# SCH_N64_SpyDVI_2024-02-24.net
KiCad netlist of a schematic drawn in EasyEDA
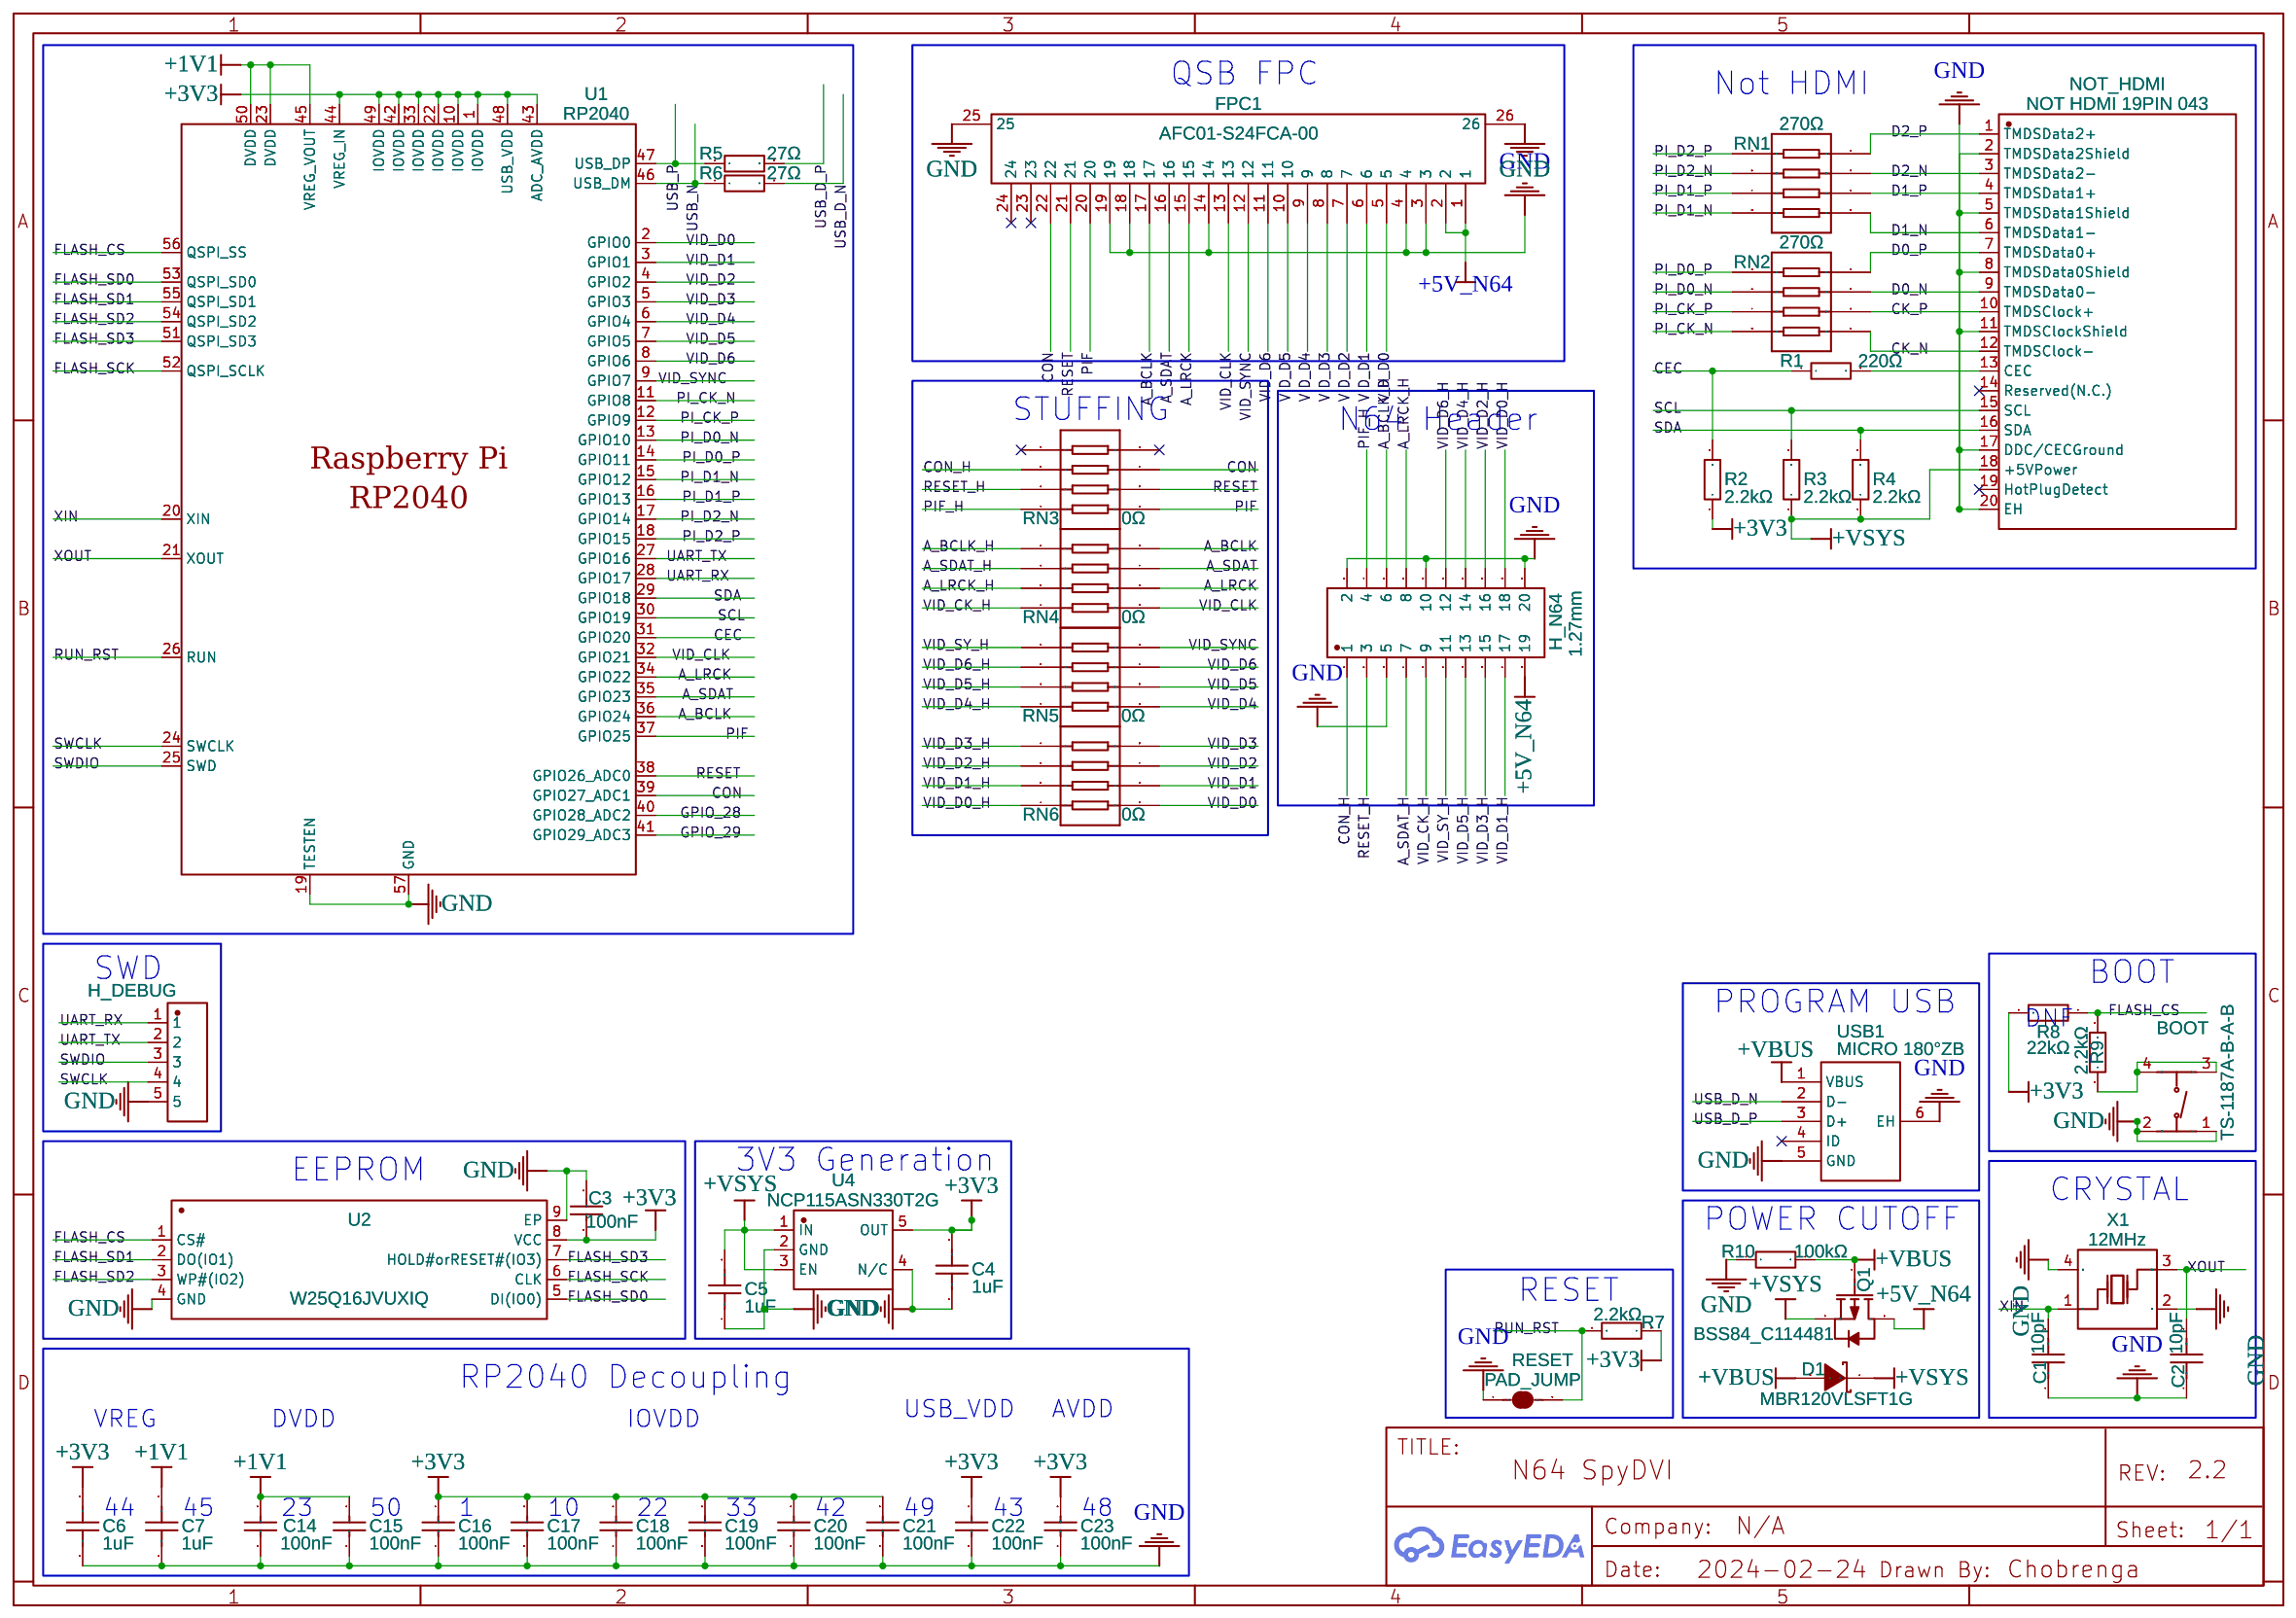
[diagram p0: schematic sheet]

(export (version "E")
  (design (tool "Eeschema 10.0.6"))
  (components
    (comp (ref "BOOT")
      (value "TS-1187A-B-A-B")
      (fields (field (name "Manufacturer") "XKB Connectivity(中国星坤)"))
      (libsource (lib "") (part "TS-1187A-B-A-B"))
    )
    (comp (ref "C1")
      (value "10pF")
      (fields
        (field (name "Manufacturer Part") "CL05C100JB5NNNC")
        (field (name "Manufacturer") "SAMSUNG(三星)")
      )
      (libsource (lib "") (part "CL05C100JB5NNNC"))
    )
    (comp (ref "C2")
      (value "10pF")
      (fields
        (field (name "Manufacturer Part") "CL05C100JB5NNNC")
        (field (name "Manufacturer") "SAMSUNG(三星)")
      )
      (libsource (lib "") (part "CL05C100JB5NNNC"))
    )
    (comp (ref "C3")
      (value "100nF")
      (fields
        (field (name "Manufacturer Part") "CL05B104KO5NNNC")
        (field (name "Manufacturer") "SAMSUNG(三星)")
      )
      (libsource (lib "") (part "CL05B104KO5NNNC"))
    )
    (comp (ref "C4")
      (value "1uF")
      (fields
        (field (name "Manufacturer Part") "CL05A105KA5NQNC")
        (field (name "Manufacturer") "SAMSUNG(三星)")
      )
      (libsource (lib "") (part "CL05A105KA5NQNC"))
    )
    (comp (ref "C5")
      (value "1uF")
      (fields
        (field (name "Manufacturer Part") "CL05A105KA5NQNC")
        (field (name "Manufacturer") "SAMSUNG(三星)")
      )
      (libsource (lib "") (part "CL05A105KA5NQNC"))
    )
    (comp (ref "C6")
      (value "1uF")
      (fields
        (field (name "Manufacturer Part") "CL05A105KA5NQNC")
        (field (name "Manufacturer") "SAMSUNG(三星)")
      )
      (libsource (lib "") (part "CL05A105KA5NQNC"))
    )
    (comp (ref "C7")
      (value "1uF")
      (fields
        (field (name "Manufacturer Part") "CL05A105KA5NQNC")
        (field (name "Manufacturer") "SAMSUNG(三星)")
      )
      (libsource (lib "") (part "CL05A105KA5NQNC"))
    )
    (comp (ref "C14")
      (value "100nF")
      (fields
        (field (name "Manufacturer Part") "CL05B104KO5NNNC")
        (field (name "Manufacturer") "SAMSUNG(三星)")
      )
      (libsource (lib "") (part "CL05B104KO5NNNC"))
    )
    (comp (ref "C15")
      (value "100nF")
      (fields
        (field (name "Manufacturer Part") "CL05B104KO5NNNC")
        (field (name "Manufacturer") "SAMSUNG(三星)")
      )
      (libsource (lib "") (part "CL05B104KO5NNNC"))
    )
    (comp (ref "C16")
      (value "100nF")
      (fields
        (field (name "Manufacturer Part") "CL05B104KO5NNNC")
        (field (name "Manufacturer") "SAMSUNG(三星)")
      )
      (libsource (lib "") (part "CL05B104KO5NNNC"))
    )
    (comp (ref "C17")
      (value "100nF")
      (fields
        (field (name "Manufacturer Part") "CL05B104KO5NNNC")
        (field (name "Manufacturer") "SAMSUNG(三星)")
      )
      (libsource (lib "") (part "CL05B104KO5NNNC"))
    )
    (comp (ref "C18")
      (value "100nF")
      (fields
        (field (name "Manufacturer Part") "CL05B104KO5NNNC")
        (field (name "Manufacturer") "SAMSUNG(三星)")
      )
      (libsource (lib "") (part "CL05B104KO5NNNC"))
    )
    (comp (ref "C19")
      (value "100nF")
      (fields
        (field (name "Manufacturer Part") "CL05B104KO5NNNC")
        (field (name "Manufacturer") "SAMSUNG(三星)")
      )
      (libsource (lib "") (part "CL05B104KO5NNNC"))
    )
    (comp (ref "C20")
      (value "100nF")
      (fields
        (field (name "Manufacturer Part") "CL05B104KO5NNNC")
        (field (name "Manufacturer") "SAMSUNG(三星)")
      )
      (libsource (lib "") (part "CL05B104KO5NNNC"))
    )
    (comp (ref "C21")
      (value "100nF")
      (fields
        (field (name "Manufacturer Part") "CL05B104KO5NNNC")
        (field (name "Manufacturer") "SAMSUNG(三星)")
      )
      (libsource (lib "") (part "CL05B104KO5NNNC"))
    )
    (comp (ref "C22")
      (value "100nF")
      (fields
        (field (name "Manufacturer Part") "CL05B104KO5NNNC")
        (field (name "Manufacturer") "SAMSUNG(三星)")
      )
      (libsource (lib "") (part "CL05B104KO5NNNC"))
    )
    (comp (ref "C23")
      (value "100nF")
      (fields
        (field (name "Manufacturer Part") "CL05B104KO5NNNC")
        (field (name "Manufacturer") "SAMSUNG(三星)")
      )
      (libsource (lib "") (part "CL05B104KO5NNNC"))
    )
    (comp (ref "D1")
      (value "MBR120VLSFT1G")
      (fields (field (name "Manufacturer") "onsemi(安森美)"))
      (libsource (lib "") (part "MBR120VLSFT1G"))
    )
    (comp (ref "FPC1")
      (value "AFC01-S24FCA-00")
      (fields (field (name "Manufacturer") "JS(钜硕电子)"))
      (libsource (lib "") (part "AFC01-S24FCA-00"))
    )
    (comp (ref "H_DEBUG")
      (value "PZ254V-11-05P")
      (fields (field (name "Manufacturer") "XFCN(兴飞)"))
      (libsource (lib "") (part "PZ254V-11-05P"))
    )
    (comp (ref "H_N64")
      (value "1.27mm")
      (fields
        (field (name "Manufacturer Part") "1.27-2*10P立贴针")
        (field (name "Manufacturer") "BOOMELE(博穆精密)")
      )
      (libsource (lib "") (part "Double row of needle2*10 1.27mm"))
    )
    (comp (ref "NOT_HDMI")
      (value "NOT HDMI 19PIN 043")
      (fields
        (field (name "Manufacturer Part") "HDMI 19PIN 043")
        (field (name "Manufacturer") "SHOU HAN(首韩)")
      )
      (libsource (lib "") (part "HDMI 19PIN 043"))
    )
    (comp (ref "Q1")
      (value "BSS84_C114481")
      (fields (field (name "Manufacturer Part") "BSS84") (field (name "Manufacturer") "CJ(江苏长电/长晶)"))
      (libsource (lib "") (part "BSS84_C114481"))
    )
    (comp (ref "R1")
      (value "220Ω")
      (fields
        (field (name "Manufacturer Part") "0402WGF2200TCE")
        (field (name "Manufacturer") "UNI-ROYAL(厚声)")
      )
      (libsource (lib "") (part "0402WGF2200TCE"))
    )
    (comp (ref "R2")
      (value "2.2kΩ")
      (fields
        (field (name "Manufacturer Part") "0402WGF2201TCE")
        (field (name "Manufacturer") "UNI-ROYAL(厚声)")
      )
      (libsource (lib "") (part "0402WGF2201TCE"))
    )
    (comp (ref "R3")
      (value "2.2kΩ")
      (fields
        (field (name "Manufacturer Part") "0402WGF2201TCE")
        (field (name "Manufacturer") "UNI-ROYAL(厚声)")
      )
      (libsource (lib "") (part "0402WGF2201TCE"))
    )
    (comp (ref "R4")
      (value "2.2kΩ")
      (fields
        (field (name "Manufacturer Part") "0402WGF2201TCE")
        (field (name "Manufacturer") "UNI-ROYAL(厚声)")
      )
      (libsource (lib "") (part "0402WGF2201TCE"))
    )
    (comp (ref "R5")
      (value "27Ω")
      (fields
        (field (name "Manufacturer Part") "0402WGF270JTCE")
        (field (name "Manufacturer") "UNI-ROYAL(厚声)")
      )
      (libsource (lib "") (part "0402WGF270JTCE"))
    )
    (comp (ref "R6")
      (value "27Ω")
      (fields
        (field (name "Manufacturer Part") "0402WGF270JTCE")
        (field (name "Manufacturer") "UNI-ROYAL(厚声)")
      )
      (libsource (lib "") (part "0402WGF270JTCE"))
    )
    (comp (ref "R7")
      (value "2.2kΩ")
      (fields
        (field (name "Manufacturer Part") "0402WGF2201TCE")
        (field (name "Manufacturer") "UNI-ROYAL(厚声)")
      )
      (libsource (lib "") (part "0402WGF2201TCE_1"))
    )
    (comp (ref "R8") (value "22kΩ") (libsource (lib "") (part "0402WGF2202TCE")))
    (comp (ref "R9")
      (value "2.2kΩ")
      (fields
        (field (name "Manufacturer Part") "0402WGF2201TCE")
        (field (name "Manufacturer") "UNI-ROYAL(厚声)")
      )
      (libsource (lib "") (part "0402WGF2201TCE"))
    )
    (comp (ref "R10")
      (value "100kΩ")
      (fields
        (field (name "Manufacturer Part") "0402WGF1003TCE")
        (field (name "Manufacturer") "UNI-ROYAL(厚声)")
      )
      (libsource (lib "") (part "0402WGF1003TCE"))
    )
    (comp (ref "RESET") (value "PAD_JUMP") (libsource (lib "") (part "JUMPER-PAD-2-NO")))
    (comp (ref "RN1")
      (value "270Ω")
      (fields (field (name "Manufacturer Part") "CAT10-271J4LF") (field (name "Manufacturer") "BOURNS"))
      (libsource (lib "") (part "CAT10-271J4LF"))
    )
    (comp (ref "RN2")
      (value "270Ω")
      (fields (field (name "Manufacturer Part") "CAT10-271J4LF") (field (name "Manufacturer") "BOURNS"))
      (libsource (lib "") (part "CAT10-271J4LF"))
    )
    (comp (ref "RN3")
      (value "0Ω")
      (fields (field (name "Manufacturer Part") "RC-MT08W000JT") (field (name "Manufacturer") "FH(风华)"))
      (libsource (lib "") (part "RC-MT08W000JT"))
    )
    (comp (ref "RN4")
      (value "0Ω")
      (fields (field (name "Manufacturer Part") "RC-MT08W000JT") (field (name "Manufacturer") "FH(风华)"))
      (libsource (lib "") (part "RC-MT08W000JT"))
    )
    (comp (ref "RN5")
      (value "0Ω")
      (fields (field (name "Manufacturer Part") "RC-MT08W000JT") (field (name "Manufacturer") "FH(风华)"))
      (libsource (lib "") (part "RC-MT08W000JT"))
    )
    (comp (ref "RN6")
      (value "0Ω")
      (fields (field (name "Manufacturer Part") "RC-MT08W000JT") (field (name "Manufacturer") "FH(风华)"))
      (libsource (lib "") (part "RC-MT08W000JT"))
    )
    (comp (ref "U1")
      (value "RP2040")
      (fields (field (name "Manufacturer") "Raspberry Pi(树莓派)"))
      (libsource (lib "") (part "RP2040"))
    )
    (comp (ref "U2")
      (value "W25Q16JVUXIQ")
      (fields (field (name "Manufacturer") "WINBOND(华邦)"))
      (libsource (lib "") (part "W25Q16JVUXIQ"))
    )
    (comp (ref "U4")
      (value "NCP115ASN330T2G")
      (fields (field (name "Manufacturer") "onsemi(安森美)"))
      (libsource (lib "") (part "NCP115ASN330T2G"))
    )
    (comp (ref "USB1")
      (value "MICRO 180°ZB")
      (fields (field (name "Manufacturer") "SHOU HAN(首韩)"))
      (libsource (lib "") (part "MICRO 180°ZB"))
    )
    (comp (ref "X1")
      (value "12MHz")
      (fields (field (name "Manufacturer Part") "X322512MMB4SI") (field (name "Manufacturer") "YXC(扬兴晶振)"))
      (libsource (lib "") (part "X322512MMB4SI"))
    )
  )
  (nets
    (net (code "1") (name "+1V1") (class "Default")
      (node (ref "C14") (pin "2") (pinfunction "2_2") (pintype "input"))
      (node (ref "C15") (pin "2") (pinfunction "2_2") (pintype "input"))
      (node (ref "C7") (pin "2") (pinfunction "2_2") (pintype "unspecified"))
      (node (ref "U1") (pin "23") (pinfunction "DVDD_23") (pintype "bidirectional"))
      (node (ref "U1") (pin "45") (pinfunction "VREG_VOUT_45") (pintype "bidirectional"))
      (node (ref "U1") (pin "50") (pinfunction "DVDD_50") (pintype "bidirectional"))
    )
    (net (code "2") (name "+3V3") (class "Default")
      (node (ref "C16") (pin "2") (pinfunction "2_2") (pintype "input"))
      (node (ref "C17") (pin "2") (pinfunction "2_2") (pintype "input"))
      (node (ref "C18") (pin "2") (pinfunction "2_2") (pintype "input"))
      (node (ref "C19") (pin "2") (pinfunction "2_2") (pintype "input"))
      (node (ref "C20") (pin "2") (pinfunction "2_2") (pintype "input"))
      (node (ref "C21") (pin "2") (pinfunction "2_2") (pintype "input"))
      (node (ref "C22") (pin "2") (pinfunction "2_2") (pintype "input"))
      (node (ref "C23") (pin "2") (pinfunction "2_2") (pintype "input"))
      (node (ref "C3") (pin "1") (pinfunction "1_1") (pintype "input"))
      (node (ref "C4") (pin "2") (pinfunction "2_2") (pintype "unspecified"))
      (node (ref "C6") (pin "2") (pinfunction "2_2") (pintype "unspecified"))
      (node (ref "R2") (pin "1") (pinfunction "1_1") (pintype "input"))
      (node (ref "R7") (pin "1") (pinfunction "1_1") (pintype "input"))
      (node (ref "R8") (pin "2") (pinfunction "2_2") (pintype "input"))
      (node (ref "U1") (pin "1") (pinfunction "IOVDD_1") (pintype "bidirectional"))
      (node (ref "U1") (pin "10") (pinfunction "IOVDD_10") (pintype "bidirectional"))
      (node (ref "U1") (pin "22") (pinfunction "IOVDD_22") (pintype "bidirectional"))
      (node (ref "U1") (pin "33") (pinfunction "IOVDD_33") (pintype "bidirectional"))
      (node (ref "U1") (pin "42") (pinfunction "IOVDD_42") (pintype "bidirectional"))
      (node (ref "U1") (pin "43") (pinfunction "ADC_AVDD_43") (pintype "bidirectional"))
      (node (ref "U1") (pin "44") (pinfunction "VREG_IN_44") (pintype "bidirectional"))
      (node (ref "U1") (pin "48") (pinfunction "USB_VDD_48") (pintype "bidirectional"))
      (node (ref "U1") (pin "49") (pinfunction "IOVDD_49") (pintype "bidirectional"))
      (node (ref "U2") (pin "8") (pinfunction "VCC_8") (pintype "unspecified"))
      (node (ref "U4") (pin "5") (pinfunction "OUT_5") (pintype "unspecified"))
    )
    (net (code "3") (name "+5V_N64") (class "Default")
      (node (ref "FPC1") (pin "1") (pinfunction "1_1") (pintype "unspecified"))
      (node (ref "FPC1") (pin "2") (pinfunction "2_2") (pintype "unspecified"))
      (node (ref "H_N64") (pin "19") (pinfunction "19_19") (pintype "unspecified"))
      (node (ref "Q1") (pin "3") (pinfunction "D_3") (pintype "unspecified"))
    )
    (net (code "4") (name "+VBUS") (class "Default")
      (node (ref "D1") (pin "2") (pinfunction "A_2") (pintype "unspecified"))
      (node (ref "Q1") (pin "1") (pinfunction "G_1") (pintype "unspecified"))
      (node (ref "R10") (pin "2") (pinfunction "2_2") (pintype "input"))
      (node (ref "USB1") (pin "1") (pinfunction "VBUS_1") (pintype "unspecified"))
    )
    (net (code "5") (name "+VSYS") (class "Default")
      (node (ref "C5") (pin "2") (pinfunction "2_2") (pintype "unspecified"))
      (node (ref "D1") (pin "1") (pinfunction "K_1") (pintype "unspecified"))
      (node (ref "NOT_HDMI") (pin "18") (pinfunction "+5VPower_18") (pintype "unspecified"))
      (node (ref "Q1") (pin "2") (pinfunction "S_2") (pintype "unspecified"))
      (node (ref "R3") (pin "1") (pinfunction "1_1") (pintype "input"))
      (node (ref "R4") (pin "1") (pinfunction "1_1") (pintype "input"))
      (node (ref "U4") (pin "1") (pinfunction "IN_1") (pintype "unspecified"))
      (node (ref "U4") (pin "3") (pinfunction "EN_3") (pintype "unspecified"))
    )
    (net (code "6") (name "/A_BCLK") (class "Default")
      (node (ref "FPC1") (pin "17") (pinfunction "17_17") (pintype "unspecified"))
      (node (ref "RN4") (pin "8") (pinfunction "8_8") (pintype "input"))
      (node (ref "U1") (pin "36") (pinfunction "GPIO24_36") (pintype "bidirectional"))
    )
    (net (code "7") (name "/A_BCLK_H") (class "Default")
      (node (ref "H_N64") (pin "6") (pinfunction "6_6") (pintype "unspecified"))
      (node (ref "RN4") (pin "1") (pinfunction "1_1") (pintype "input"))
    )
    (net (code "8") (name "/A_LRCK") (class "Default")
      (node (ref "FPC1") (pin "15") (pinfunction "15_15") (pintype "unspecified"))
      (node (ref "RN4") (pin "6") (pinfunction "6_6") (pintype "input"))
      (node (ref "U1") (pin "34") (pinfunction "GPIO22_34") (pintype "bidirectional"))
    )
    (net (code "9") (name "/A_LRCK_H") (class "Default")
      (node (ref "H_N64") (pin "8") (pinfunction "8_8") (pintype "unspecified"))
      (node (ref "RN4") (pin "3") (pinfunction "3_3") (pintype "input"))
    )
    (net (code "10") (name "/A_SDAT") (class "Default")
      (node (ref "FPC1") (pin "16") (pinfunction "16_16") (pintype "unspecified"))
      (node (ref "RN4") (pin "7") (pinfunction "7_7") (pintype "input"))
      (node (ref "U1") (pin "35") (pinfunction "GPIO23_35") (pintype "bidirectional"))
    )
    (net (code "11") (name "/A_SDAT_H") (class "Default")
      (node (ref "H_N64") (pin "7") (pinfunction "7_7") (pintype "unspecified"))
      (node (ref "RN4") (pin "2") (pinfunction "2_2") (pintype "input"))
    )
    (net (code "12") (name "/CEC") (class "Default")
      (node (ref "R1") (pin "1") (pinfunction "1_1") (pintype "input"))
      (node (ref "R2") (pin "2") (pinfunction "2_2") (pintype "input"))
      (node (ref "U1") (pin "31") (pinfunction "GPIO20_31") (pintype "bidirectional"))
    )
    (net (code "13") (name "/CK_N") (class "Default")
      (node (ref "NOT_HDMI") (pin "12") (pinfunction "TMDSClock-_12") (pintype "unspecified"))
      (node (ref "RN2") (pin "1") (pinfunction "1_1") (pintype "input"))
    )
    (net (code "14") (name "/CK_P") (class "Default")
      (node (ref "NOT_HDMI") (pin "10") (pinfunction "TMDSClock+_10") (pintype "unspecified"))
      (node (ref "RN2") (pin "2") (pinfunction "2_2") (pintype "input"))
    )
    (net (code "15") (name "/CON") (class "Default")
      (node (ref "FPC1") (pin "22") (pinfunction "22_22") (pintype "unspecified"))
      (node (ref "RN3") (pin "7") (pinfunction "7_7") (pintype "input"))
      (node (ref "U1") (pin "39") (pinfunction "GPIO27_ADC1_39") (pintype "bidirectional"))
    )
    (net (code "16") (name "/CON_H") (class "Default")
      (node (ref "H_N64") (pin "1") (pinfunction "1_1") (pintype "unspecified"))
      (node (ref "RN3") (pin "2") (pinfunction "2_2") (pintype "input"))
    )
    (net (code "17") (name "/D0_N") (class "Default")
      (node (ref "NOT_HDMI") (pin "9") (pinfunction "TMDSData0-_9") (pintype "unspecified"))
      (node (ref "RN2") (pin "3") (pinfunction "3_3") (pintype "input"))
    )
    (net (code "18") (name "/D0_P") (class "Default")
      (node (ref "NOT_HDMI") (pin "7") (pinfunction "TMDSData0+_7") (pintype "unspecified"))
      (node (ref "RN2") (pin "4") (pinfunction "4_4") (pintype "input"))
    )
    (net (code "19") (name "/D1_N") (class "Default")
      (node (ref "NOT_HDMI") (pin "6") (pinfunction "TMDSData1-_6") (pintype "unspecified"))
      (node (ref "RN1") (pin "1") (pinfunction "1_1") (pintype "input"))
    )
    (net (code "20") (name "/D1_P") (class "Default")
      (node (ref "NOT_HDMI") (pin "4") (pinfunction "TMDSData1+_4") (pintype "unspecified"))
      (node (ref "RN1") (pin "2") (pinfunction "2_2") (pintype "input"))
    )
    (net (code "21") (name "/D2_N") (class "Default")
      (node (ref "NOT_HDMI") (pin "3") (pinfunction "TMDSData2-_3") (pintype "unspecified"))
      (node (ref "RN1") (pin "3") (pinfunction "3_3") (pintype "input"))
    )
    (net (code "22") (name "/D2_P") (class "Default")
      (node (ref "NOT_HDMI") (pin "1") (pinfunction "TMDSData2+_1") (pintype "unspecified"))
      (node (ref "RN1") (pin "4") (pinfunction "4_4") (pintype "input"))
    )
    (net (code "23") (name "/FLASH_CS") (class "Default")
      (node (ref "R8") (pin "1") (pinfunction "1_1") (pintype "input"))
      (node (ref "R9") (pin "2") (pinfunction "2_2") (pintype "input"))
      (node (ref "U1") (pin "56") (pinfunction "QSPI_SS_56") (pintype "bidirectional"))
      (node (ref "U2") (pin "1") (pinfunction "CS#_1") (pintype "unspecified"))
    )
    (net (code "24") (name "/FLASH_SCK") (class "Default")
      (node (ref "U1") (pin "52") (pinfunction "QSPI_SCLK_52") (pintype "output"))
      (node (ref "U2") (pin "6") (pinfunction "CLK_6") (pintype "unspecified"))
    )
    (net (code "25") (name "/FLASH_SD0") (class "Default")
      (node (ref "U1") (pin "53") (pinfunction "QSPI_SD0_53") (pintype "bidirectional"))
      (node (ref "U2") (pin "5") (pinfunction "DI(IO0)_5") (pintype "unspecified"))
    )
    (net (code "26") (name "/FLASH_SD1") (class "Default")
      (node (ref "U1") (pin "55") (pinfunction "QSPI_SD1_55") (pintype "bidirectional"))
      (node (ref "U2") (pin "2") (pinfunction "DO(IO1)_2") (pintype "unspecified"))
    )
    (net (code "27") (name "/FLASH_SD2") (class "Default")
      (node (ref "U1") (pin "54") (pinfunction "QSPI_SD2_54") (pintype "bidirectional"))
      (node (ref "U2") (pin "3") (pinfunction "WP#(IO2)_3") (pintype "unspecified"))
    )
    (net (code "28") (name "/FLASH_SD3") (class "Default")
      (node (ref "U1") (pin "51") (pinfunction "QSPI_SD3_51") (pintype "bidirectional"))
      (node (ref "U2") (pin "7") (pinfunction "HOLD#orRESET#(IO3)_7") (pintype "unspecified"))
    )
    (net (code "29") (name "/GPIO_28") (class "Default")
      (node (ref "U1") (pin "40") (pinfunction "GPIO28_ADC2_40") (pintype "bidirectional"))
    )
    (net (code "30") (name "/GPIO_29") (class "Default")
      (node (ref "U1") (pin "41") (pinfunction "GPIO29_ADC3_41") (pintype "bidirectional"))
    )
    (net (code "31") (name "/PIF") (class "Default")
      (node (ref "FPC1") (pin "20") (pinfunction "20_20") (pintype "unspecified"))
      (node (ref "RN3") (pin "5") (pinfunction "5_5") (pintype "input"))
      (node (ref "U1") (pin "37") (pinfunction "GPIO25_37") (pintype "bidirectional"))
    )
    (net (code "32") (name "/PIF_H") (class "Default")
      (node (ref "H_N64") (pin "4") (pinfunction "4_4") (pintype "unspecified"))
      (node (ref "RN3") (pin "4") (pinfunction "4_4") (pintype "input"))
    )
    (net (code "33") (name "/PI_CK_N") (class "Default")
      (node (ref "RN2") (pin "8") (pinfunction "8_8") (pintype "input"))
      (node (ref "U1") (pin "11") (pinfunction "GPIO8_11") (pintype "bidirectional"))
    )
    (net (code "34") (name "/PI_CK_P") (class "Default")
      (node (ref "RN2") (pin "7") (pinfunction "7_7") (pintype "input"))
      (node (ref "U1") (pin "12") (pinfunction "GPIO9_12") (pintype "bidirectional"))
    )
    (net (code "35") (name "/PI_D0_N") (class "Default")
      (node (ref "RN2") (pin "6") (pinfunction "6_6") (pintype "input"))
      (node (ref "U1") (pin "13") (pinfunction "GPIO10_13") (pintype "bidirectional"))
    )
    (net (code "36") (name "/PI_D0_P") (class "Default")
      (node (ref "RN2") (pin "5") (pinfunction "5_5") (pintype "input"))
      (node (ref "U1") (pin "14") (pinfunction "GPIO11_14") (pintype "bidirectional"))
    )
    (net (code "37") (name "/PI_D1_N") (class "Default")
      (node (ref "RN1") (pin "8") (pinfunction "8_8") (pintype "input"))
      (node (ref "U1") (pin "15") (pinfunction "GPIO12_15") (pintype "bidirectional"))
    )
    (net (code "38") (name "/PI_D1_P") (class "Default")
      (node (ref "RN1") (pin "7") (pinfunction "7_7") (pintype "input"))
      (node (ref "U1") (pin "16") (pinfunction "GPIO13_16") (pintype "bidirectional"))
    )
    (net (code "39") (name "/PI_D2_N") (class "Default")
      (node (ref "RN1") (pin "6") (pinfunction "6_6") (pintype "input"))
      (node (ref "U1") (pin "17") (pinfunction "GPIO14_17") (pintype "bidirectional"))
    )
    (net (code "40") (name "/PI_D2_P") (class "Default")
      (node (ref "RN1") (pin "5") (pinfunction "5_5") (pintype "input"))
      (node (ref "U1") (pin "18") (pinfunction "GPIO15_18") (pintype "bidirectional"))
    )
    (net (code "41") (name "/RESET") (class "Default")
      (node (ref "FPC1") (pin "21") (pinfunction "21_21") (pintype "unspecified"))
      (node (ref "RN3") (pin "6") (pinfunction "6_6") (pintype "input"))
      (node (ref "U1") (pin "38") (pinfunction "GPIO26_ADC0_38") (pintype "bidirectional"))
    )
    (net (code "42") (name "/RESET_H") (class "Default")
      (node (ref "H_N64") (pin "3") (pinfunction "3_3") (pintype "unspecified"))
      (node (ref "RN3") (pin "3") (pinfunction "3_3") (pintype "input"))
    )
    (net (code "43") (name "/RUN_RST") (class "Default")
      (node (ref "R7") (pin "2") (pinfunction "2_2") (pintype "input"))
      (node (ref "RESET") (pin "2") (pinfunction "2_2") (pintype "unspecified"))
      (node (ref "U1") (pin "26") (pinfunction "RUN_26") (pintype "input"))
    )
    (net (code "44") (name "/SCL") (class "Default")
      (node (ref "NOT_HDMI") (pin "15") (pinfunction "SCL_15") (pintype "unspecified"))
      (node (ref "R3") (pin "2") (pinfunction "2_2") (pintype "input"))
      (node (ref "U1") (pin "30") (pinfunction "GPIO19_30") (pintype "bidirectional"))
    )
    (net (code "45") (name "/SDA") (class "Default")
      (node (ref "NOT_HDMI") (pin "16") (pinfunction "SDA_16") (pintype "unspecified"))
      (node (ref "R4") (pin "2") (pinfunction "2_2") (pintype "input"))
      (node (ref "U1") (pin "29") (pinfunction "GPIO18_29") (pintype "bidirectional"))
    )
    (net (code "46") (name "/SWCLK") (class "Default")
      (node (ref "H_DEBUG") (pin "4") (pinfunction "4_4") (pintype "unspecified"))
      (node (ref "U1") (pin "24") (pinfunction "SWCLK_24") (pintype "output"))
    )
    (net (code "47") (name "/SWDIO") (class "Default")
      (node (ref "H_DEBUG") (pin "3") (pinfunction "3_3") (pintype "unspecified"))
      (node (ref "U1") (pin "25") (pinfunction "SWD_25") (pintype "bidirectional"))
    )
    (net (code "48") (name "/UART_RX") (class "Default")
      (node (ref "H_DEBUG") (pin "1") (pinfunction "1_1") (pintype "unspecified"))
      (node (ref "U1") (pin "28") (pinfunction "GPIO17_28") (pintype "bidirectional"))
    )
    (net (code "49") (name "/UART_TX") (class "Default")
      (node (ref "H_DEBUG") (pin "2") (pinfunction "2_2") (pintype "unspecified"))
      (node (ref "U1") (pin "27") (pinfunction "GPIO16_27") (pintype "bidirectional"))
    )
    (net (code "50") (name "/USB_D_N") (class "Default")
      (node (ref "R6") (pin "2") (pinfunction "2_2") (pintype "input"))
      (node (ref "USB1") (pin "2") (pinfunction "D-_2") (pintype "unspecified"))
    )
    (net (code "51") (name "/USB_D_P") (class "Default")
      (node (ref "R5") (pin "2") (pinfunction "2_2") (pintype "input"))
      (node (ref "USB1") (pin "3") (pinfunction "D+_3") (pintype "unspecified"))
    )
    (net (code "52") (name "/USB_N") (class "Default")
      (node (ref "R6") (pin "1") (pinfunction "1_1") (pintype "input"))
      (node (ref "U1") (pin "46") (pinfunction "USB_DM_46") (pintype "bidirectional"))
    )
    (net (code "53") (name "/USB_P") (class "Default")
      (node (ref "R5") (pin "1") (pinfunction "1_1") (pintype "input"))
      (node (ref "U1") (pin "47") (pinfunction "USB_DP_47") (pintype "bidirectional"))
    )
    (net (code "54") (name "/VID_CK_H") (class "Default")
      (node (ref "H_N64") (pin "9") (pinfunction "9_9") (pintype "unspecified"))
      (node (ref "RN4") (pin "4") (pinfunction "4_4") (pintype "input"))
    )
    (net (code "55") (name "/VID_CLK") (class "Default")
      (node (ref "FPC1") (pin "13") (pinfunction "13_13") (pintype "unspecified"))
      (node (ref "RN4") (pin "5") (pinfunction "5_5") (pintype "input"))
      (node (ref "U1") (pin "32") (pinfunction "GPIO21_32") (pintype "bidirectional"))
    )
    (net (code "56") (name "/VID_D0") (class "Default")
      (node (ref "FPC1") (pin "5") (pinfunction "5_5") (pintype "unspecified"))
      (node (ref "RN6") (pin "5") (pinfunction "5_5") (pintype "input"))
      (node (ref "U1") (pin "2") (pinfunction "GPIO0_2") (pintype "bidirectional"))
    )
    (net (code "57") (name "/VID_D0_H") (class "Default")
      (node (ref "H_N64") (pin "18") (pinfunction "18_18") (pintype "unspecified"))
      (node (ref "RN6") (pin "4") (pinfunction "4_4") (pintype "input"))
    )
    (net (code "58") (name "/VID_D1") (class "Default")
      (node (ref "FPC1") (pin "6") (pinfunction "6_6") (pintype "unspecified"))
      (node (ref "RN6") (pin "6") (pinfunction "6_6") (pintype "input"))
      (node (ref "U1") (pin "3") (pinfunction "GPIO1_3") (pintype "bidirectional"))
    )
    (net (code "59") (name "/VID_D1_H") (class "Default")
      (node (ref "H_N64") (pin "17") (pinfunction "17_17") (pintype "unspecified"))
      (node (ref "RN6") (pin "3") (pinfunction "3_3") (pintype "input"))
    )
    (net (code "60") (name "/VID_D2") (class "Default")
      (node (ref "FPC1") (pin "7") (pinfunction "7_7") (pintype "unspecified"))
      (node (ref "RN6") (pin "7") (pinfunction "7_7") (pintype "input"))
      (node (ref "U1") (pin "4") (pinfunction "GPIO2_4") (pintype "bidirectional"))
    )
    (net (code "61") (name "/VID_D2_H") (class "Default")
      (node (ref "H_N64") (pin "16") (pinfunction "16_16") (pintype "unspecified"))
      (node (ref "RN6") (pin "2") (pinfunction "2_2") (pintype "input"))
    )
    (net (code "62") (name "/VID_D3") (class "Default")
      (node (ref "FPC1") (pin "8") (pinfunction "8_8") (pintype "unspecified"))
      (node (ref "RN6") (pin "8") (pinfunction "8_8") (pintype "input"))
      (node (ref "U1") (pin "5") (pinfunction "GPIO3_5") (pintype "bidirectional"))
    )
    (net (code "63") (name "/VID_D3_H") (class "Default")
      (node (ref "H_N64") (pin "15") (pinfunction "15_15") (pintype "unspecified"))
      (node (ref "RN6") (pin "1") (pinfunction "1_1") (pintype "input"))
    )
    (net (code "64") (name "/VID_D4") (class "Default")
      (node (ref "FPC1") (pin "9") (pinfunction "9_9") (pintype "unspecified"))
      (node (ref "RN5") (pin "5") (pinfunction "5_5") (pintype "input"))
      (node (ref "U1") (pin "6") (pinfunction "GPIO4_6") (pintype "bidirectional"))
    )
    (net (code "65") (name "/VID_D4_H") (class "Default")
      (node (ref "H_N64") (pin "14") (pinfunction "14_14") (pintype "unspecified"))
      (node (ref "RN5") (pin "4") (pinfunction "4_4") (pintype "input"))
    )
    (net (code "66") (name "/VID_D5") (class "Default")
      (node (ref "FPC1") (pin "10") (pinfunction "10_10") (pintype "unspecified"))
      (node (ref "RN5") (pin "6") (pinfunction "6_6") (pintype "input"))
      (node (ref "U1") (pin "7") (pinfunction "GPIO5_7") (pintype "bidirectional"))
    )
    (net (code "67") (name "/VID_D5_H") (class "Default")
      (node (ref "H_N64") (pin "13") (pinfunction "13_13") (pintype "unspecified"))
      (node (ref "RN5") (pin "3") (pinfunction "3_3") (pintype "input"))
    )
    (net (code "68") (name "/VID_D6") (class "Default")
      (node (ref "FPC1") (pin "11") (pinfunction "11_11") (pintype "unspecified"))
      (node (ref "RN5") (pin "7") (pinfunction "7_7") (pintype "input"))
      (node (ref "U1") (pin "8") (pinfunction "GPIO6_8") (pintype "bidirectional"))
    )
    (net (code "69") (name "/VID_D6_H") (class "Default")
      (node (ref "H_N64") (pin "12") (pinfunction "12_12") (pintype "unspecified"))
      (node (ref "RN5") (pin "2") (pinfunction "2_2") (pintype "input"))
    )
    (net (code "70") (name "/VID_SYNC") (class "Default")
      (node (ref "FPC1") (pin "12") (pinfunction "12_12") (pintype "unspecified"))
      (node (ref "RN5") (pin "8") (pinfunction "8_8") (pintype "input"))
      (node (ref "U1") (pin "9") (pinfunction "GPIO7_9") (pintype "bidirectional"))
    )
    (net (code "71") (name "/VID_SY_H") (class "Default")
      (node (ref "H_N64") (pin "11") (pinfunction "11_11") (pintype "unspecified"))
      (node (ref "RN5") (pin "1") (pinfunction "1_1") (pintype "input"))
    )
    (net (code "72") (name "/XIN") (class "Default")
      (node (ref "C1") (pin "2") (pinfunction "2_2") (pintype "unspecified"))
      (node (ref "U1") (pin "20") (pinfunction "XIN_20") (pintype "input"))
      (node (ref "X1") (pin "1") (pinfunction "OSC1_1") (pintype "unspecified"))
    )
    (net (code "73") (name "/XOUT") (class "Default")
      (node (ref "C2") (pin "2") (pinfunction "2_2") (pintype "unspecified"))
      (node (ref "U1") (pin "21") (pinfunction "XOUT_21") (pintype "unspecified"))
      (node (ref "X1") (pin "3") (pinfunction "OSC2_3") (pintype "unspecified"))
    )
    (net (code "74") (name "GND") (class "Default")
      (node (ref "BOOT") (pin "1") (pinfunction "A_1") (pintype "unspecified"))
      (node (ref "BOOT") (pin "2") (pinfunction "B_2") (pintype "unspecified"))
      (node (ref "C1") (pin "1") (pinfunction "1_1") (pintype "unspecified"))
      (node (ref "C14") (pin "1") (pinfunction "1_1") (pintype "input"))
      (node (ref "C15") (pin "1") (pinfunction "1_1") (pintype "input"))
      (node (ref "C16") (pin "1") (pinfunction "1_1") (pintype "input"))
      (node (ref "C17") (pin "1") (pinfunction "1_1") (pintype "input"))
      (node (ref "C18") (pin "1") (pinfunction "1_1") (pintype "input"))
      (node (ref "C19") (pin "1") (pinfunction "1_1") (pintype "input"))
      (node (ref "C2") (pin "1") (pinfunction "1_1") (pintype "unspecified"))
      (node (ref "C20") (pin "1") (pinfunction "1_1") (pintype "input"))
      (node (ref "C21") (pin "1") (pinfunction "1_1") (pintype "input"))
      (node (ref "C22") (pin "1") (pinfunction "1_1") (pintype "input"))
      (node (ref "C23") (pin "1") (pinfunction "1_1") (pintype "input"))
      (node (ref "C3") (pin "2") (pinfunction "2_2") (pintype "input"))
      (node (ref "C4") (pin "1") (pinfunction "1_1") (pintype "unspecified"))
      (node (ref "C5") (pin "1") (pinfunction "1_1") (pintype "unspecified"))
      (node (ref "C6") (pin "1") (pinfunction "1_1") (pintype "unspecified"))
      (node (ref "C7") (pin "1") (pinfunction "1_1") (pintype "unspecified"))
      (node (ref "FPC1") (pin "14") (pinfunction "14_14") (pintype "unspecified"))
      (node (ref "FPC1") (pin "18") (pinfunction "18_18") (pintype "unspecified"))
      (node (ref "FPC1") (pin "19") (pinfunction "19_19") (pintype "unspecified"))
      (node (ref "FPC1") (pin "25") (pinfunction "25_25") (pintype "unspecified"))
      (node (ref "FPC1") (pin "26") (pinfunction "26_26") (pintype "unspecified"))
      (node (ref "FPC1") (pin "3") (pinfunction "3_3") (pintype "unspecified"))
      (node (ref "FPC1") (pin "4") (pinfunction "4_4") (pintype "unspecified"))
      (node (ref "H_DEBUG") (pin "5") (pinfunction "5_5") (pintype "unspecified"))
      (node (ref "H_N64") (pin "10") (pinfunction "10_10") (pintype "unspecified"))
      (node (ref "H_N64") (pin "2") (pinfunction "2_2") (pintype "unspecified"))
      (node (ref "H_N64") (pin "20") (pinfunction "20_20") (pintype "unspecified"))
      (node (ref "H_N64") (pin "5") (pinfunction "5_5") (pintype "unspecified"))
      (node (ref "NOT_HDMI") (pin "11") (pinfunction "TMDSClockShield_11") (pintype "unspecified"))
      (node (ref "NOT_HDMI") (pin "17") (pinfunction "DDC/CECGround_17") (pintype "unspecified"))
      (node (ref "NOT_HDMI") (pin "2") (pinfunction "TMDSData2Shield_2") (pintype "unspecified"))
      (node (ref "NOT_HDMI") (pin "20") (pinfunction "EH_20") (pintype "unspecified"))
      (node (ref "NOT_HDMI") (pin "5") (pinfunction "TMDSData1Shield_5") (pintype "unspecified"))
      (node (ref "NOT_HDMI") (pin "8") (pinfunction "TMDSData0Shield_8") (pintype "unspecified"))
      (node (ref "R10") (pin "1") (pinfunction "1_1") (pintype "input"))
      (node (ref "RESET") (pin "1") (pinfunction "1_1") (pintype "unspecified"))
      (node (ref "U1") (pin "19") (pinfunction "TESTEN_19") (pintype "unspecified"))
      (node (ref "U1") (pin "57") (pinfunction "GND_57") (pintype "bidirectional"))
      (node (ref "U2") (pin "4") (pinfunction "GND_4") (pintype "unspecified"))
      (node (ref "U2") (pin "9") (pinfunction "EP_9") (pintype "unspecified"))
      (node (ref "U4") (pin "2") (pinfunction "GND_2") (pintype "unspecified"))
      (node (ref "U4") (pin "4") (pinfunction "N/C_4") (pintype "unspecified"))
      (node (ref "USB1") (pin "5") (pinfunction "GND_5") (pintype "unspecified"))
      (node (ref "USB1") (pin "6") (pinfunction "EH_6") (pintype "unspecified"))
      (node (ref "X1") (pin "2") (pinfunction "GND_2") (pintype "unspecified"))
      (node (ref "X1") (pin "4") (pinfunction "GND_4") (pintype "unspecified"))
    )
    (net (code "75") (name "Net-(BOOT-C)") (class "Default")
      (node (ref "BOOT") (pin "3") (pinfunction "C_3") (pintype "unspecified"))
      (node (ref "BOOT") (pin "4") (pinfunction "D_4") (pintype "unspecified"))
      (node (ref "R9") (pin "1") (pinfunction "1_1") (pintype "input"))
    )
    (net (code "76") (name "Net-(NOT_HDMI-CEC)") (class "Default")
      (node (ref "NOT_HDMI") (pin "13") (pinfunction "CEC_13") (pintype "unspecified"))
      (node (ref "R1") (pin "2") (pinfunction "2_2") (pintype "input"))
    )
    (net (code "77") (name "unconnected-(FPC1-Pad23)") (class "Default")
      (node (ref "FPC1") (pin "23") (pinfunction "23_23") (pintype "unspecified+no_connect"))
    )
    (net (code "78") (name "unconnected-(FPC1-Pad24)") (class "Default")
      (node (ref "FPC1") (pin "24") (pinfunction "24_24") (pintype "unspecified+no_connect"))
    )
    (net (code "79") (name "unconnected-(NOT_HDMI-HotPlugDetect-Pad19)") (class "Default")
      (node (ref "NOT_HDMI") (pin "19") (pinfunction "HotPlugDetect_19") (pintype "unspecified+no_connect"))
    )
    (net (code "80") (name "unconnected-(NOT_HDMI-Reserved(N.C.)-Pad14)") (class "Default")
      (node (ref "NOT_HDMI") (pin "14") (pinfunction "Reserved(N.C.)_14") (pintype "unspecified+no_connect"))
    )
    (net (code "81") (name "unconnected-(RN3-Pad1)") (class "Default")
      (node (ref "RN3") (pin "1") (pinfunction "1_1") (pintype "input+no_connect"))
    )
    (net (code "82") (name "unconnected-(RN3-Pad8)") (class "Default")
      (node (ref "RN3") (pin "8") (pinfunction "8_8") (pintype "input+no_connect"))
    )
    (net (code "83") (name "unconnected-(USB1-ID-Pad4)") (class "Default")
      (node (ref "USB1") (pin "4") (pinfunction "ID_4") (pintype "unspecified+no_connect"))
    )
  )
)
